# STAC_Breakout_PCB.net
KiCad netlist of a schematic drawn in Altium Designer
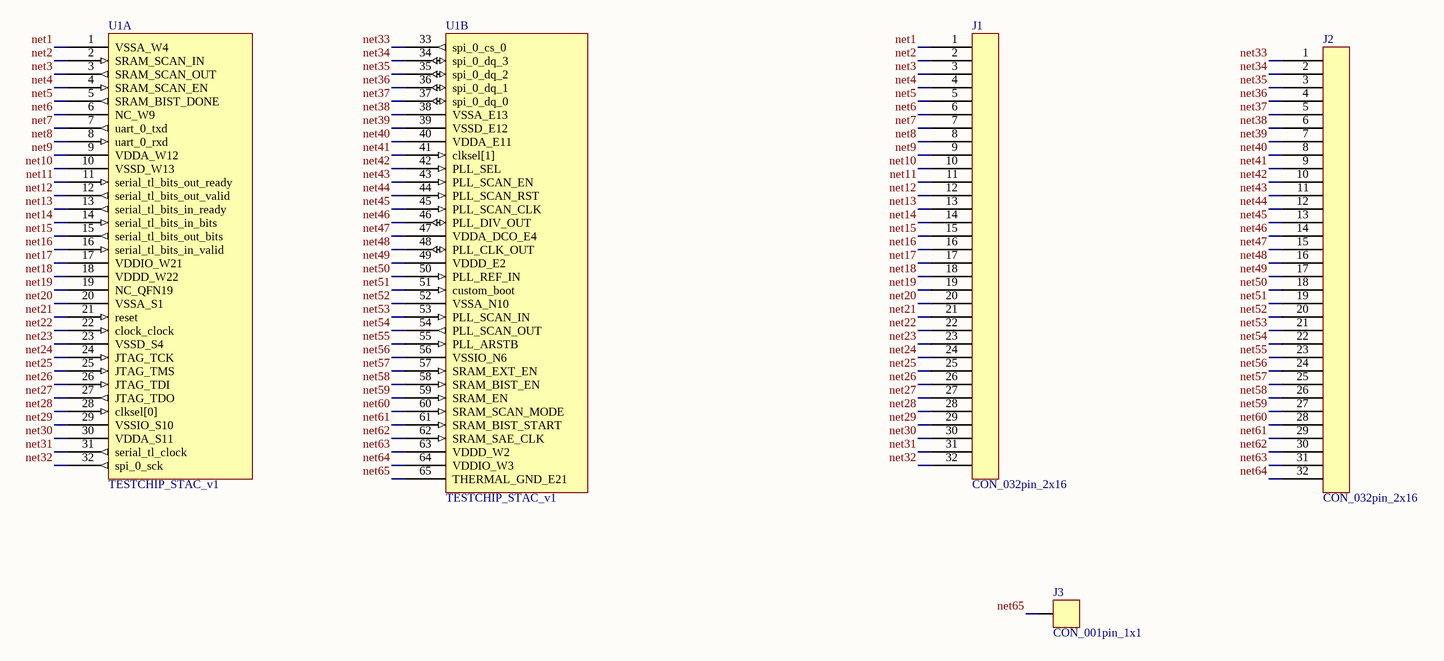
[diagram p0: STAC_Breakout_PCB.SchDoc]

(export (version "E")
  (design (tool "Eeschema 10.0.6"))
  (components
    (comp (ref "J1")
      (value "CON_032pin_2x16")
      (footprint "CON-032-100-1600X200/2X16-POST")
      (libsource (lib "BWRC") (part "CON_032pin_2x16"))
    )
    (comp (ref "J2")
      (value "CON_032pin_2x16")
      (footprint "CON-032-100-1600X200/2X16-POST")
      (libsource (lib "BWRC") (part "CON_032pin_2x16"))
    )
    (comp (ref "J3")
      (value "CON_001pin_1x1")
      (footprint "CON-001-100-100X100/1X1-POST")
      (description "Con 1 pin")
      (libsource (lib "BWRC") (part "CON_001pin_1x1"))
    )
    (comp (ref "U1")
      (value "TESTCHIP_STAC_v1")
      (footprint "BWRC:STAC-QFN-64-.5-9.0X9.0/THERM-7.6")
      (description "TESTCHIP STAC v1")
      (libsource (lib "BWRC") (part "TESTCHIP_STAC_v1"))
    )
  )
  (nets
    (net (code "1") (name "/net1") (class "Default")
      (node (ref "J1") (pin "1") (pintype "passive"))
      (node (ref "U1") (pin "1") (pinfunction "VSSA_W4_1") (pintype "power_in"))
    )
    (net (code "2") (name "/net2") (class "Default")
      (node (ref "J1") (pin "2") (pintype "passive"))
      (node (ref "U1") (pin "2") (pinfunction "SRAM_SCAN_IN_2") (pintype "input"))
    )
    (net (code "3") (name "/net3") (class "Default")
      (node (ref "J1") (pin "3") (pintype "passive"))
      (node (ref "U1") (pin "3") (pinfunction "SRAM_SCAN_OUT_3") (pintype "output"))
    )
    (net (code "4") (name "/net4") (class "Default")
      (node (ref "J1") (pin "4") (pintype "passive"))
      (node (ref "U1") (pin "4") (pinfunction "SRAM_SCAN_EN_4") (pintype "input"))
    )
    (net (code "5") (name "/net5") (class "Default")
      (node (ref "J1") (pin "5") (pintype "passive"))
      (node (ref "U1") (pin "5") (pinfunction "SRAM_BIST_DONE_5") (pintype "output"))
    )
    (net (code "6") (name "/net6") (class "Default")
      (node (ref "J1") (pin "6") (pintype "passive"))
      (node (ref "U1") (pin "6") (pinfunction "NC_W9_6") (pintype "tri_state"))
    )
    (net (code "7") (name "/net7") (class "Default")
      (node (ref "J1") (pin "7") (pintype "passive"))
      (node (ref "U1") (pin "7") (pinfunction "uart_0_txd_7") (pintype "output"))
    )
    (net (code "8") (name "/net8") (class "Default")
      (node (ref "J1") (pin "8") (pintype "passive"))
      (node (ref "U1") (pin "8") (pinfunction "uart_0_rxd_8") (pintype "input"))
    )
    (net (code "9") (name "/net9") (class "Default")
      (node (ref "J1") (pin "9") (pintype "passive"))
      (node (ref "U1") (pin "9") (pinfunction "VDDA_W12_9") (pintype "power_in"))
    )
    (net (code "10") (name "/net10") (class "Default")
      (node (ref "J1") (pin "10") (pintype "passive"))
      (node (ref "U1") (pin "10") (pinfunction "VSSD_W13_10") (pintype "power_in"))
    )
    (net (code "11") (name "/net11") (class "Default")
      (node (ref "J1") (pin "11") (pintype "passive"))
      (node (ref "U1") (pin "11") (pinfunction "serial_tl_bits_out_ready_11") (pintype "input"))
    )
    (net (code "12") (name "/net12") (class "Default")
      (node (ref "J1") (pin "12") (pintype "passive"))
      (node (ref "U1") (pin "12") (pinfunction "serial_tl_bits_out_valid_12") (pintype "output"))
    )
    (net (code "13") (name "/net13") (class "Default")
      (node (ref "J1") (pin "13") (pintype "passive"))
      (node (ref "U1") (pin "13") (pinfunction "serial_tl_bits_in_ready_13") (pintype "output"))
    )
    (net (code "14") (name "/net14") (class "Default")
      (node (ref "J1") (pin "14") (pintype "passive"))
      (node (ref "U1") (pin "14") (pinfunction "serial_tl_bits_in_bits_14") (pintype "input"))
    )
    (net (code "15") (name "/net15") (class "Default")
      (node (ref "J1") (pin "15") (pintype "passive"))
      (node (ref "U1") (pin "15") (pinfunction "serial_tl_bits_out_bits_15") (pintype "output"))
    )
    (net (code "16") (name "/net16") (class "Default")
      (node (ref "J1") (pin "16") (pintype "passive"))
      (node (ref "U1") (pin "16") (pinfunction "serial_tl_bits_in_valid_16") (pintype "input"))
    )
    (net (code "17") (name "/net17") (class "Default")
      (node (ref "J1") (pin "17") (pintype "passive"))
      (node (ref "U1") (pin "17") (pinfunction "VDDIO_W21_17") (pintype "power_in"))
    )
    (net (code "18") (name "/net18") (class "Default")
      (node (ref "J1") (pin "18") (pintype "passive"))
      (node (ref "U1") (pin "18") (pinfunction "VDDD_W22_18") (pintype "power_in"))
    )
    (net (code "19") (name "/net19") (class "Default")
      (node (ref "J1") (pin "19") (pintype "passive"))
      (node (ref "U1") (pin "19") (pinfunction "NC_QFN19_19") (pintype "tri_state"))
    )
    (net (code "20") (name "/net20") (class "Default")
      (node (ref "J1") (pin "20") (pintype "passive"))
      (node (ref "U1") (pin "20") (pinfunction "VSSA_S1_20") (pintype "power_in"))
    )
    (net (code "21") (name "/net21") (class "Default")
      (node (ref "J1") (pin "21") (pintype "passive"))
      (node (ref "U1") (pin "21") (pinfunction "reset_21") (pintype "input"))
    )
    (net (code "22") (name "/net22") (class "Default")
      (node (ref "J1") (pin "22") (pintype "passive"))
      (node (ref "U1") (pin "22") (pinfunction "clock_clock_22") (pintype "input"))
    )
    (net (code "23") (name "/net23") (class "Default")
      (node (ref "J1") (pin "23") (pintype "passive"))
      (node (ref "U1") (pin "23") (pinfunction "VSSD_S4_23") (pintype "power_in"))
    )
    (net (code "24") (name "/net24") (class "Default")
      (node (ref "J1") (pin "24") (pintype "passive"))
      (node (ref "U1") (pin "24") (pinfunction "JTAG_TCK_24") (pintype "input"))
    )
    (net (code "25") (name "/net25") (class "Default")
      (node (ref "J1") (pin "25") (pintype "passive"))
      (node (ref "U1") (pin "25") (pinfunction "JTAG_TMS_25") (pintype "input"))
    )
    (net (code "26") (name "/net26") (class "Default")
      (node (ref "J1") (pin "26") (pintype "passive"))
      (node (ref "U1") (pin "26") (pinfunction "JTAG_TDI_26") (pintype "input"))
    )
    (net (code "27") (name "/net27") (class "Default")
      (node (ref "J1") (pin "27") (pintype "passive"))
      (node (ref "U1") (pin "27") (pinfunction "JTAG_TDO_27") (pintype "output"))
    )
    (net (code "28") (name "/net28") (class "Default")
      (node (ref "J1") (pin "28") (pintype "passive"))
      (node (ref "U1") (pin "28") (pinfunction "clksel[0]_28") (pintype "input"))
    )
    (net (code "29") (name "/net29") (class "Default")
      (node (ref "J1") (pin "29") (pintype "passive"))
      (node (ref "U1") (pin "29") (pinfunction "VSSIO_S10_29") (pintype "power_in"))
    )
    (net (code "30") (name "/net30") (class "Default")
      (node (ref "J1") (pin "30") (pintype "passive"))
      (node (ref "U1") (pin "30") (pinfunction "VDDA_S11_30") (pintype "power_in"))
    )
    (net (code "31") (name "/net31") (class "Default")
      (node (ref "J1") (pin "31") (pintype "passive"))
      (node (ref "U1") (pin "31") (pinfunction "serial_tl_clock_31") (pintype "output"))
    )
    (net (code "32") (name "/net32") (class "Default")
      (node (ref "J1") (pin "32") (pintype "passive"))
      (node (ref "U1") (pin "32") (pinfunction "spi_0_sck_32") (pintype "output"))
    )
    (net (code "33") (name "/net33") (class "Default")
      (node (ref "J2") (pin "1") (pintype "passive"))
      (node (ref "U1") (pin "33") (pinfunction "spi_0_cs_0_33") (pintype "output"))
    )
    (net (code "34") (name "/net34") (class "Default")
      (node (ref "J2") (pin "2") (pintype "passive"))
      (node (ref "U1") (pin "34") (pinfunction "spi_0_dq_3_34") (pintype "bidirectional"))
    )
    (net (code "35") (name "/net35") (class "Default")
      (node (ref "J2") (pin "3") (pintype "passive"))
      (node (ref "U1") (pin "35") (pinfunction "spi_0_dq_2_35") (pintype "bidirectional"))
    )
    (net (code "36") (name "/net36") (class "Default")
      (node (ref "J2") (pin "4") (pintype "passive"))
      (node (ref "U1") (pin "36") (pinfunction "spi_0_dq_1_36") (pintype "bidirectional"))
    )
    (net (code "37") (name "/net37") (class "Default")
      (node (ref "J2") (pin "5") (pintype "passive"))
      (node (ref "U1") (pin "37") (pinfunction "spi_0_dq_0_37") (pintype "bidirectional"))
    )
    (net (code "38") (name "/net38") (class "Default")
      (node (ref "J2") (pin "6") (pintype "passive"))
      (node (ref "U1") (pin "38") (pinfunction "VSSA_E13_38") (pintype "power_in"))
    )
    (net (code "39") (name "/net39") (class "Default")
      (node (ref "J2") (pin "7") (pintype "passive"))
      (node (ref "U1") (pin "39") (pinfunction "VSSD_E12_39") (pintype "power_in"))
    )
    (net (code "40") (name "/net40") (class "Default")
      (node (ref "J2") (pin "8") (pintype "passive"))
      (node (ref "U1") (pin "40") (pinfunction "VDDA_E11_40") (pintype "power_in"))
    )
    (net (code "41") (name "/net41") (class "Default")
      (node (ref "J2") (pin "9") (pintype "passive"))
      (node (ref "U1") (pin "41") (pinfunction "clksel[1]_41") (pintype "input"))
    )
    (net (code "42") (name "/net42") (class "Default")
      (node (ref "J2") (pin "10") (pintype "passive"))
      (node (ref "U1") (pin "42") (pinfunction "PLL_SEL_42") (pintype "input"))
    )
    (net (code "43") (name "/net43") (class "Default")
      (node (ref "J2") (pin "11") (pintype "passive"))
      (node (ref "U1") (pin "43") (pinfunction "PLL_SCAN_EN_43") (pintype "input"))
    )
    (net (code "44") (name "/net44") (class "Default")
      (node (ref "J2") (pin "12") (pintype "passive"))
      (node (ref "U1") (pin "44") (pinfunction "PLL_SCAN_RST_44") (pintype "input"))
    )
    (net (code "45") (name "/net45") (class "Default")
      (node (ref "J2") (pin "13") (pintype "passive"))
      (node (ref "U1") (pin "45") (pinfunction "PLL_SCAN_CLK_45") (pintype "input"))
    )
    (net (code "46") (name "/net46") (class "Default")
      (node (ref "J2") (pin "14") (pintype "passive"))
      (node (ref "U1") (pin "46") (pinfunction "PLL_DIV_OUT_46") (pintype "bidirectional"))
    )
    (net (code "47") (name "/net47") (class "Default")
      (node (ref "J2") (pin "15") (pintype "passive"))
      (node (ref "U1") (pin "47") (pinfunction "VDDA_DCO_E4_47") (pintype "power_in"))
    )
    (net (code "48") (name "/net48") (class "Default")
      (node (ref "J2") (pin "16") (pintype "passive"))
      (node (ref "U1") (pin "48") (pinfunction "PLL_CLK_OUT_48") (pintype "bidirectional"))
    )
    (net (code "49") (name "/net49") (class "Default")
      (node (ref "J2") (pin "17") (pintype "passive"))
      (node (ref "U1") (pin "49") (pinfunction "VDDD_E2_49") (pintype "power_in"))
    )
    (net (code "50") (name "/net50") (class "Default")
      (node (ref "J2") (pin "18") (pintype "passive"))
      (node (ref "U1") (pin "50") (pinfunction "PLL_REF_IN_50") (pintype "input"))
    )
    (net (code "51") (name "/net51") (class "Default")
      (node (ref "J2") (pin "19") (pintype "passive"))
      (node (ref "U1") (pin "51") (pinfunction "custom_boot_51") (pintype "input"))
    )
    (net (code "52") (name "/net52") (class "Default")
      (node (ref "J2") (pin "20") (pintype "passive"))
      (node (ref "U1") (pin "52") (pinfunction "VSSA_N10_52") (pintype "power_in"))
    )
    (net (code "53") (name "/net53") (class "Default")
      (node (ref "J2") (pin "21") (pintype "passive"))
      (node (ref "U1") (pin "53") (pinfunction "PLL_SCAN_IN_53") (pintype "input"))
    )
    (net (code "54") (name "/net54") (class "Default")
      (node (ref "J2") (pin "22") (pintype "passive"))
      (node (ref "U1") (pin "54") (pinfunction "PLL_SCAN_OUT_54") (pintype "output"))
    )
    (net (code "55") (name "/net55") (class "Default")
      (node (ref "J2") (pin "23") (pintype "passive"))
      (node (ref "U1") (pin "55") (pinfunction "PLL_ARSTB_55") (pintype "input"))
    )
    (net (code "56") (name "/net56") (class "Default")
      (node (ref "J2") (pin "24") (pintype "passive"))
      (node (ref "U1") (pin "56") (pinfunction "VSSIO_N6_56") (pintype "power_in"))
    )
    (net (code "57") (name "/net57") (class "Default")
      (node (ref "J2") (pin "25") (pintype "passive"))
      (node (ref "U1") (pin "57") (pinfunction "SRAM_EXT_EN_57") (pintype "input"))
    )
    (net (code "58") (name "/net58") (class "Default")
      (node (ref "J2") (pin "26") (pintype "passive"))
      (node (ref "U1") (pin "58") (pinfunction "SRAM_BIST_EN_58") (pintype "input"))
    )
    (net (code "59") (name "/net59") (class "Default")
      (node (ref "J2") (pin "27") (pintype "passive"))
      (node (ref "U1") (pin "59") (pinfunction "SRAM_EN_59") (pintype "input"))
    )
    (net (code "60") (name "/net60") (class "Default")
      (node (ref "J2") (pin "28") (pintype "passive"))
      (node (ref "U1") (pin "60") (pinfunction "SRAM_SCAN_MODE_60") (pintype "input"))
    )
    (net (code "61") (name "/net61") (class "Default")
      (node (ref "J2") (pin "29") (pintype "passive"))
      (node (ref "U1") (pin "61") (pinfunction "SRAM_BIST_START_61") (pintype "input"))
    )
    (net (code "62") (name "/net62") (class "Default")
      (node (ref "J2") (pin "30") (pintype "passive"))
      (node (ref "U1") (pin "62") (pinfunction "SRAM_SAE_CLK_62") (pintype "input"))
    )
    (net (code "63") (name "/net63") (class "Default")
      (node (ref "J2") (pin "31") (pintype "passive"))
      (node (ref "U1") (pin "63") (pinfunction "VDDD_W2_63") (pintype "power_in"))
    )
    (net (code "64") (name "/net64") (class "Default")
      (node (ref "J2") (pin "32") (pintype "passive"))
      (node (ref "U1") (pin "64") (pinfunction "VDDIO_W3_64") (pintype "power_in"))
    )
    (net (code "65") (name "/net65") (class "Default")
      (node (ref "J3") (pin "1") (pinfunction "1_1") (pintype "passive"))
      (node (ref "U1") (pin "65") (pinfunction "THERMAL_GND_E21_65") (pintype "power_in"))
    )
  )
)
